# ST_LINK_V2-1.net
KiCad netlist of a schematic drawn in Altium Designer
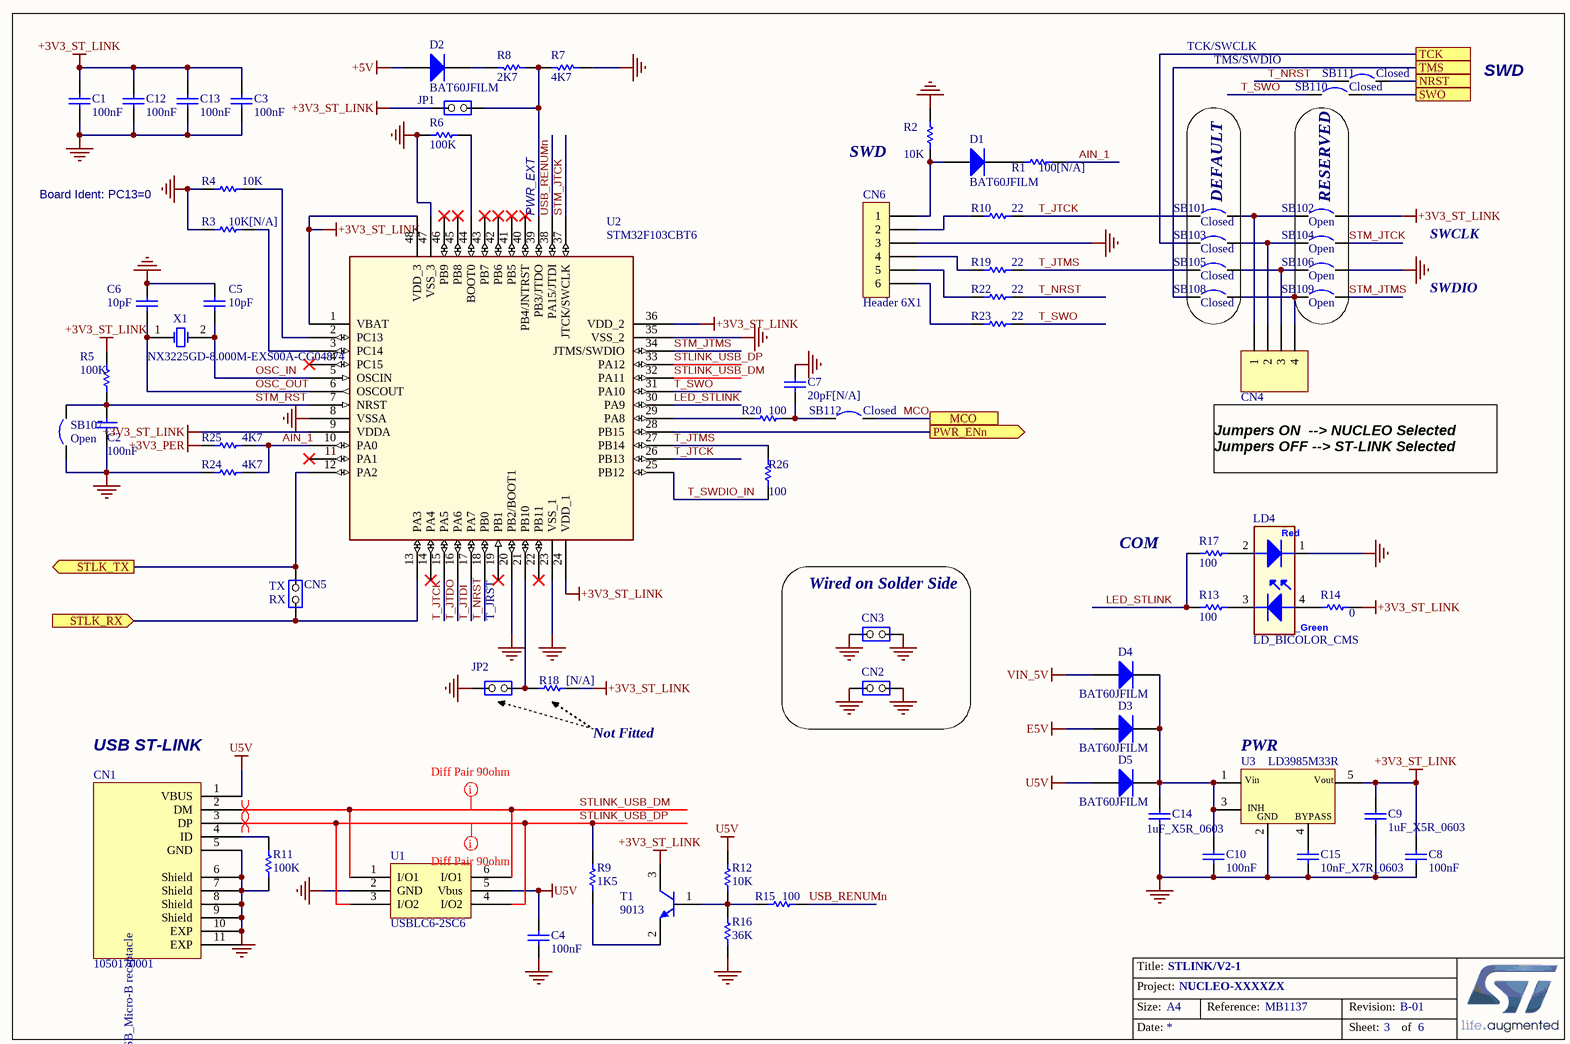
[diagram p0: ST_LINK_V2-1.SCHDOC]

(export (version "E")
  (design (tool "Eeschema 10.0.6"))
  (components
    (comp (ref "C1")
      (value "100nF")
      (footprint "0603C")
      (description "Capacitor 0402 / 0603 / 0805")
      (libsource (lib "MCD_TOOLS") (part "Capacitor_ST"))
    )
    (comp (ref "C2")
      (value "100nF")
      (footprint "0603C")
      (description "Capacitor 0402 / 0603 / 0805")
      (libsource (lib "MCD_TOOLS") (part "Capacitor_ST"))
    )
    (comp (ref "C3")
      (value "100nF")
      (footprint "0603C")
      (description "Capacitor 0402 / 0603 / 0805")
      (libsource (lib "MCD_TOOLS") (part "Capacitor_ST"))
    )
    (comp (ref "C4")
      (value "100nF")
      (footprint "0603C")
      (description "Capacitor 0402 / 0603 / 0805")
      (libsource (lib "MCD_TOOLS") (part "Capacitor_ST"))
    )
    (comp (ref "C5")
      (value "10pF")
      (footprint "0603C")
      (description "Capacitor 0402 / 0603 / 0805")
      (libsource (lib "MCD_TOOLS") (part "Capacitor_ST"))
    )
    (comp (ref "C6")
      (value "10pF")
      (footprint "0603C")
      (description "Capacitor 0402 / 0603 / 0805")
      (libsource (lib "MCD_TOOLS") (part "Capacitor_ST"))
    )
    (comp (ref "C7")
      (value "20pF[N/A]")
      (footprint "0603C")
      (description "Capacitor 0402 / 0603 / 0805")
      (libsource (lib "MCD_TOOLS") (part "Capacitor_ST"))
    )
    (comp (ref "C8")
      (value "100nF")
      (footprint "0603C")
      (description "Capacitor 0402 / 0603 / 0805")
      (libsource (lib "MCD_TOOLS") (part "Capacitor_ST"))
    )
    (comp (ref "C9")
      (value "1uF_X5R_0603")
      (footprint "0603C")
      (description "0603  X5R 1µF")
      (fields (field (name "TOLERANCE") "10%"))
      (libsource (lib "MB963_1") (part "CAP SMD 0603  X5R 1µF 25V 10%"))
    )
    (comp (ref "C10")
      (value "100nF")
      (footprint "0603C")
      (description "Capacitor 0402 / 0603 / 0805")
      (libsource (lib "MCD_TOOLS") (part "Capacitor_ST"))
    )
    (comp (ref "C12")
      (value "100nF")
      (footprint "0603C")
      (description "Capacitor 0402 / 0603 / 0805")
      (libsource (lib "MCD_TOOLS") (part "Capacitor_ST"))
    )
    (comp (ref "C13")
      (value "100nF")
      (footprint "0603C")
      (description "Capacitor 0402 / 0603 / 0805")
      (libsource (lib "MCD_TOOLS") (part "Capacitor_ST"))
    )
    (comp (ref "C14")
      (value "1uF_X5R_0603")
      (footprint "0603C")
      (description "0603  X5R 1µF")
      (fields (field (name "TOLERANCE") "10%"))
      (libsource (lib "MB963_1") (part "CAP SMD 0603  X5R 1µF 25V 10%"))
    )
    (comp (ref "C15")
      (value "10nF_X7R_0603")
      (footprint "0603C")
      (description "0603  X7R 10NF")
      (fields (field (name "TOLERANCE") "10%"))
      (libsource (lib "MB963_1") (part "CAP SMD 0603  X7R 10000PF 50V 10%"))
    )
    (comp (ref "CN1")
      (value "1050170001")
      (footprint "Molex_1050170001")
      (libsource (lib "Smartphone_accessory") (part "1050170001"))
    )
    (comp (ref "CN2") (value "~") (footprint "HDR_1x2_2R54_V_M") (libsource (lib "*") (part "JP2")))
    (comp (ref "CN3") (value "~") (footprint "HDR_1x2_2R54_V_M") (libsource (lib "*") (part "JP2")))
    (comp (ref "CN4")
      (value "Header 4")
      (footprint "HDR_1x4_2R54_V_M")
      (description "Header, 4-Pin, Single row")
      (fields (field (name "PUBLISHER") "Altium Limited"))
      (libsource (lib "Nucleo_64") (part "Header 4"))
    )
    (comp (ref "CN5") (value "~") (footprint "HDR_1x2_2R54_V_M_S") (libsource (lib "MCD_TOOLS") (part "JP2")))
    (comp (ref "CN6")
      (value "Header 6X1")
      (footprint "HDR_1x6_2R54_V_M")
      (description "Header, 6-Pin, Single row")
      (fields (field (name "PUBLISHER") "Altium Limited"))
      (libsource (lib "Nucleo_64") (part "Header 6X1"))
    )
    (comp (ref "D1")
      (value "BAT60JFILM")
      (footprint "SOD-323")
      (libsource (lib "MB1137") (part "BAT60JFILM"))
    )
    (comp (ref "D2")
      (value "BAT60JFILM")
      (footprint "SOD-323")
      (description "Default Diode")
      (fields (field (name "PUBLISHER") "Altium Limited"))
      (libsource (lib "MB1144_1") (part "Diode"))
    )
    (comp (ref "D3")
      (value "BAT60JFILM")
      (footprint "SOD-323")
      (libsource (lib "MB1137") (part "BAT60JFILM"))
    )
    (comp (ref "D4")
      (value "BAT60JFILM")
      (footprint "SOD-323")
      (libsource (lib "MB1137") (part "BAT60JFILM"))
    )
    (comp (ref "D5")
      (value "BAT60JFILM")
      (footprint "SOD-323")
      (libsource (lib "MB1137") (part "BAT60JFILM"))
    )
    (comp (ref "JP1") (value "~") (footprint "HDR_1x2_2R54_V_M_S") (libsource (lib "*") (part "JP2")))
    (comp (ref "JP2") (value "~") (footprint "HDR_1x2_2R54_V_M_S") (libsource (lib "*") (part "JP2")))
    (comp (ref "LD4")
      (value "LD_BICOLOR_CMS")
      (footprint "HSMF-A201")
      (description "Bicolor Led")
      (libsource (lib "MB1137") (part "LD_BICOLOR_CMS"))
    )
    (comp (ref "R1")
      (value "100[N/A]")
      (footprint "0603R")
      (description "Resistor 0402 / 0603 / 0805")
      (libsource (lib "") (part "Res1_1"))
    )
    (comp (ref "R2")
      (value "10K")
      (footprint "0603R")
      (description "Resistor 0402 / 0603 / 0805")
      (libsource (lib "") (part "Res1_1"))
    )
    (comp (ref "R3")
      (value "10K[N/A]")
      (footprint "0603R")
      (description "Resistor 0402 / 0603 / 0805")
      (libsource (lib "") (part "Res1_1"))
    )
    (comp (ref "R4")
      (value "10K")
      (footprint "0603R")
      (description "Resistor 0402 / 0603 / 0805")
      (libsource (lib "") (part "Res1_1"))
    )
    (comp (ref "R5")
      (value "100K")
      (footprint "0603R")
      (description "Resistor 0402 / 0603 / 0805")
      (libsource (lib "") (part "Res1_1"))
    )
    (comp (ref "R6")
      (value "100K")
      (footprint "0603R")
      (description "Resistor 0402 / 0603 / 0805")
      (libsource (lib "") (part "Res1_1"))
    )
    (comp (ref "R7")
      (value "4K7")
      (footprint "0603R")
      (description "Resistor")
      (fields (field (name "PUBLISHER") "Altium Limited"))
      (libsource (lib "Miscellaneous Devices") (part "Res1"))
    )
    (comp (ref "R8")
      (value "2K7")
      (footprint "0603R")
      (description "Resistor")
      (fields (field (name "PUBLISHER") "Altium Limited"))
      (libsource (lib "Miscellaneous Devices") (part "Res1"))
    )
    (comp (ref "R9")
      (value "1K5")
      (footprint "0603R")
      (description "Resistor 0402 / 0603 / 0805")
      (libsource (lib "") (part "Res1_1"))
    )
    (comp (ref "R10")
      (value "22")
      (footprint "0603R")
      (description "Resistor 0402 / 0603 / 0805")
      (libsource (lib "") (part "Res1_1"))
    )
    (comp (ref "R11")
      (value "100K")
      (footprint "0603R")
      (description "Resistor 0402 / 0603 / 0805")
      (libsource (lib "") (part "Res1_1"))
    )
    (comp (ref "R12")
      (value "10K")
      (footprint "0603R")
      (description "Resistor")
      (fields (field (name "PUBLISHER") "Altium Limited"))
      (libsource (lib "") (part "Res1_2"))
    )
    (comp (ref "R13")
      (value "100")
      (footprint "0603R")
      (description "Resistor 0402 / 0603 / 0805")
      (libsource (lib "") (part "Res1_1"))
    )
    (comp (ref "R14")
      (value "0")
      (footprint "0603R")
      (description "Resistor 0402 / 0603 / 0805")
      (libsource (lib "") (part "Res1_1"))
    )
    (comp (ref "R15")
      (value "100")
      (footprint "0603R")
      (description "Resistor 0402 / 0603 / 0805")
      (libsource (lib "") (part "Res1_1"))
    )
    (comp (ref "R16")
      (value "36K")
      (footprint "0603R")
      (description "Resistor")
      (fields (field (name "PUBLISHER") "Altium Limited"))
      (libsource (lib "") (part "Res1_2"))
    )
    (comp (ref "R17")
      (value "100")
      (footprint "0603R")
      (description "Resistor 0402 / 0603 / 0805")
      (libsource (lib "") (part "Res1_1"))
    )
    (comp (ref "R18")
      (value "[N/A]")
      (footprint "0603R")
      (description "Resistor")
      (fields (field (name "PUBLISHER") "Altium Limited"))
      (libsource (lib "") (part "Res1_2"))
    )
    (comp (ref "R19")
      (value "22")
      (footprint "0603R")
      (description "Resistor 0402 / 0603 / 0805")
      (libsource (lib "") (part "Res1_1"))
    )
    (comp (ref "R20")
      (value "100")
      (footprint "0603R")
      (description "Resistor 0402 / 0603 / 0805")
      (libsource (lib "") (part "Res1_1"))
    )
    (comp (ref "R22")
      (value "22")
      (footprint "0603R")
      (description "Resistor 0402 / 0603 / 0805")
      (libsource (lib "") (part "Res1_1"))
    )
    (comp (ref "R23")
      (value "22")
      (footprint "0603R")
      (description "Resistor 0402 / 0603 / 0805")
      (libsource (lib "") (part "Res1_1"))
    )
    (comp (ref "R24")
      (value "4K7")
      (footprint "0603R")
      (description "Resistor 0402 / 0603 / 0805")
      (libsource (lib "") (part "Res1_1"))
    )
    (comp (ref "R25")
      (value "4K7")
      (footprint "0603R")
      (description "Resistor 0402 / 0603 / 0805")
      (libsource (lib "") (part "Res1_1"))
    )
    (comp (ref "R26")
      (value "100")
      (footprint "0603R")
      (description "Resistor 0402 / 0603 / 0805")
      (libsource (lib "") (part "Res1_1"))
    )
    (comp (ref "SB101")
      (value "Closed")
      (footprint "SB_0603")
      (description "Circuit Breaker")
      (fields (field (name "PUBLISHER") "Altium Limited"))
      (libsource (lib "MB1167") (part "Circuit Breaker_close"))
    )
    (comp (ref "SB102")
      (value "Open")
      (footprint "SB_0603")
      (description "Circuit Breaker")
      (fields (field (name "PUBLISHER") "Altium Limited"))
      (libsource (lib "MB1167") (part "Circuit Breaker"))
    )
    (comp (ref "SB103")
      (value "Closed")
      (footprint "SB_0603")
      (description "Circuit Breaker")
      (fields (field (name "PUBLISHER") "Altium Limited"))
      (libsource (lib "MB1167") (part "Circuit Breaker_close"))
    )
    (comp (ref "SB104")
      (value "Open")
      (footprint "SB_0603")
      (description "Circuit Breaker")
      (fields (field (name "PUBLISHER") "Altium Limited"))
      (libsource (lib "MB1167") (part "Circuit Breaker"))
    )
    (comp (ref "SB105")
      (value "Closed")
      (footprint "SB_0603")
      (description "Circuit Breaker")
      (fields (field (name "PUBLISHER") "Altium Limited"))
      (libsource (lib "MB1167") (part "Circuit Breaker_close"))
    )
    (comp (ref "SB106")
      (value "Open")
      (footprint "SB_0603")
      (description "Circuit Breaker")
      (fields (field (name "PUBLISHER") "Altium Limited"))
      (libsource (lib "MB1167") (part "Circuit Breaker"))
    )
    (comp (ref "SB107")
      (value "Open")
      (footprint "SB_0603")
      (description "Circuit Breaker")
      (fields (field (name "PUBLISHER") "Altium Limited"))
      (libsource (lib "MB1167") (part "Circuit Breaker"))
    )
    (comp (ref "SB108")
      (value "Closed")
      (footprint "SB_0603")
      (description "Circuit Breaker")
      (fields (field (name "PUBLISHER") "Altium Limited"))
      (libsource (lib "MB1167") (part "Circuit Breaker_close"))
    )
    (comp (ref "SB109")
      (value "Open")
      (footprint "SB_0603")
      (description "Circuit Breaker")
      (fields (field (name "PUBLISHER") "Altium Limited"))
      (libsource (lib "MB1167") (part "Circuit Breaker"))
    )
    (comp (ref "SB110")
      (value "Closed")
      (footprint "SB_0603")
      (description "Circuit Breaker")
      (fields (field (name "PUBLISHER") "Altium Limited"))
      (libsource (lib "MB1167") (part "Circuit Breaker_close"))
    )
    (comp (ref "SB111")
      (value "Closed")
      (footprint "SB_0603")
      (description "Circuit Breaker")
      (fields (field (name "PUBLISHER") "Altium Limited"))
      (libsource (lib "MB1167") (part "Circuit Breaker_close"))
    )
    (comp (ref "SB112")
      (value "Closed")
      (footprint "SB_0603")
      (description "Circuit Breaker")
      (fields (field (name "PUBLISHER") "Altium Limited"))
      (libsource (lib "MB1167") (part "Circuit Breaker_close"))
    )
    (comp (ref "T1")
      (value "9013")
      (footprint "SOT-23")
      (description "NPN Bipolar Transistor")
      (fields (field (name "PUBLISHER") "Altium Limited"))
      (libsource (lib "MB1167") (part "NPN"))
    )
    (comp (ref "U1")
      (value "USBLC6-2SC6")
      (footprint "SOT23-6L")
      (libsource (lib "MB1137") (part "USBLC6-2SC6"))
    )
    (comp (ref "U2")
      (value "STM32F103CBT6")
      (footprint "LQFP48_0R5_7x7")
      (description "Medium-density performance line ARM-based 32-bit MCU with 64KB Flash")
      (libsource (lib "Nucleo_64") (part "STM32F103CBT6"))
    )
    (comp (ref "U3")
      (value "LD3985M33R")
      (footprint "SOT-23-5L")
      (description "Ultra low drop-low noise BiCMOS voltage, regulators low ESR capacitors compatible")
      (libsource (lib "MCD_TOOLS") (part "LD3985M33R"))
    )
    (comp (ref "X1")
      (value "NX3225GD-8.000M-EXS00A-CG04874")
      (footprint "OSC_2SM_3R2x2R5")
      (description "Crystal Oscillator")
      (fields (field (name "PUBLISHER") "Altium Limited"))
      (libsource (lib "MB963_1") (part "XTAL"))
    )
  )
  (nets
    (net (code "1") (name "+3V3_PER") (class "Default")
      (node (ref "R25") (pin "1") (pinfunction "1_1") (pintype "passive"))
    )
    (net (code "2") (name "+3V3_ST_LINK") (class "Default")
      (node (ref "C1") (pin "2") (pinfunction "2_2") (pintype "passive"))
      (node (ref "C12") (pin "2") (pinfunction "2_2") (pintype "passive"))
      (node (ref "C13") (pin "2") (pinfunction "2_2") (pintype "passive"))
      (node (ref "C3") (pin "2") (pinfunction "2_2") (pintype "passive"))
      (node (ref "C8") (pin "2") (pinfunction "2_2") (pintype "passive"))
      (node (ref "C9") (pin "1") (pinfunction "1_1") (pintype "passive"))
      (node (ref "JP1") (pin "1") (pinfunction "COMMON_1") (pintype "passive"))
      (node (ref "R14") (pin "2") (pinfunction "2_2") (pintype "passive"))
      (node (ref "R18") (pin "1") (pinfunction "1_1") (pintype "passive"))
      (node (ref "R5") (pin "2") (pinfunction "2_2") (pintype "passive"))
      (node (ref "SB102") (pin "2") (pinfunction "2_2") (pintype "passive"))
      (node (ref "T1") (pin "3") (pinfunction "C_3") (pintype "passive"))
      (node (ref "U2") (pin "1") (pinfunction "VBAT_1") (pintype "power_in"))
      (node (ref "U2") (pin "24") (pinfunction "VDD_1_24") (pintype "power_in"))
      (node (ref "U2") (pin "36") (pinfunction "VDD_2_36") (pintype "power_in"))
      (node (ref "U2") (pin "48") (pinfunction "VDD_3_48") (pintype "power_in"))
      (node (ref "U2") (pin "9") (pinfunction "VDDA_9") (pintype "power_in"))
      (node (ref "U3") (pin "5") (pinfunction "Vout_5") (pintype "passive"))
    )
    (net (code "3") (name "+5V") (class "Default")
      (node (ref "D2") (pin "1") (pinfunction "A_1") (pintype "passive"))
    )
    (net (code "4") (name "/AIN_1") (class "Default")
      (node (ref "R1") (pin "2") (pinfunction "2_2") (pintype "passive"))
      (node (ref "R24") (pin "2") (pinfunction "2_2") (pintype "passive"))
      (node (ref "R25") (pin "2") (pinfunction "2_2") (pintype "passive"))
      (node (ref "U2") (pin "10") (pinfunction "PA0_10") (pintype "bidirectional"))
    )
    (net (code "5") (name "/LED_STLINK") (class "Default")
      (node (ref "R13") (pin "1") (pinfunction "1_1") (pintype "passive"))
      (node (ref "R17") (pin "1") (pinfunction "1_1") (pintype "passive"))
      (node (ref "U2") (pin "30") (pinfunction "PA9_30") (pintype "bidirectional"))
    )
    (net (code "6") (name "/MCO") (class "Default")
      (node (ref "SB112") (pin "2") (pinfunction "2_2") (pintype "passive"))
    )
    (net (code "7") (name "/NRST") (class "Default")
      (node (ref "SB111") (pin "2") (pinfunction "2_2") (pintype "passive"))
    )
    (net (code "8") (name "/OSC_IN") (class "Default")
      (node (ref "C5") (pin "1") (pinfunction "1_1") (pintype "passive"))
      (node (ref "U2") (pin "5") (pinfunction "OSCIN_5") (pintype "input"))
      (node (ref "X1") (pin "2") (pinfunction "OSC2_2") (pintype "passive"))
    )
    (net (code "9") (name "/OSC_OUT") (class "Default")
      (node (ref "C6") (pin "1") (pinfunction "1_1") (pintype "passive"))
      (node (ref "U2") (pin "6") (pinfunction "OSCOUT_6") (pintype "output"))
      (node (ref "X1") (pin "1") (pinfunction "OSC1_1") (pintype "passive"))
    )
    (net (code "10") (name "/PWR_ENn") (class "Default")
      (node (ref "U2") (pin "28") (pinfunction "PB15_28") (pintype "bidirectional"))
    )
    (net (code "11") (name "/STLINK_USB_DM") (class "Default")
      (node (ref "CN1") (pin "2") (pinfunction "DM_2") (pintype "passive"))
      (node (ref "U1") (pin "1") (pinfunction "I/O1_1") (pintype "passive"))
      (node (ref "U1") (pin "6") (pinfunction "I/O1_6") (pintype "passive"))
      (node (ref "U2") (pin "32") (pinfunction "PA11_32") (pintype "bidirectional"))
    )
    (net (code "12") (name "/STLINK_USB_DP") (class "Default")
      (node (ref "CN1") (pin "3") (pinfunction "DP_3") (pintype "passive"))
      (node (ref "R9") (pin "1") (pinfunction "1_1") (pintype "passive"))
      (node (ref "U1") (pin "3") (pinfunction "I/O2_3") (pintype "passive"))
      (node (ref "U1") (pin "4") (pinfunction "I/O2_4") (pintype "passive"))
      (node (ref "U2") (pin "33") (pinfunction "PA12_33") (pintype "bidirectional"))
    )
    (net (code "13") (name "/STLK_RX") (class "Default")
      (node (ref "CN5") (pin "1") (pinfunction "COMMON_1") (pintype "passive"))
      (node (ref "U2") (pin "13") (pinfunction "PA3_13") (pintype "bidirectional"))
    )
    (net (code "14") (name "/STLK_TX") (class "Default")
      (node (ref "CN5") (pin "2") (pinfunction "NO_2") (pintype "passive"))
      (node (ref "U2") (pin "12") (pinfunction "PA2_12") (pintype "bidirectional"))
    )
    (net (code "15") (name "/STM_JTCK") (class "Default")
      (node (ref "SB104") (pin "2") (pinfunction "2_2") (pintype "passive"))
      (node (ref "U2") (pin "37") (pinfunction "JTCK/SWCLK_37") (pintype "bidirectional"))
    )
    (net (code "16") (name "/STM_JTMS") (class "Default")
      (node (ref "SB109") (pin "2") (pinfunction "2_2") (pintype "passive"))
      (node (ref "U2") (pin "34") (pinfunction "JTMS/SWDIO_34") (pintype "bidirectional"))
    )
    (net (code "17") (name "/STM_RST") (class "Default")
      (node (ref "C2") (pin "2") (pinfunction "2_2") (pintype "passive"))
      (node (ref "R5") (pin "1") (pinfunction "1_1") (pintype "passive"))
      (node (ref "SB107") (pin "2") (pinfunction "2_2") (pintype "passive"))
      (node (ref "U2") (pin "7") (pinfunction "NRST_7") (pintype "input"))
    )
    (net (code "18") (name "/SWO") (class "Default")
      (node (ref "SB110") (pin "2") (pinfunction "2_2") (pintype "passive"))
    )
    (net (code "19") (name "/TCK") (class "Default")
      (node (ref "SB103") (pin "1") (pinfunction "1_1") (pintype "passive"))
    )
    (net (code "20") (name "/TMS") (class "Default")
      (node (ref "SB108") (pin "1") (pinfunction "1_1") (pintype "passive"))
    )
    (net (code "21") (name "/T_JTCK") (class "Default")
      (node (ref "R10") (pin "2") (pinfunction "2_2") (pintype "passive"))
      (node (ref "SB101") (pin "1") (pinfunction "1_1") (pintype "passive"))
      (node (ref "U2") (pin "15") (pinfunction "PA5_15") (pintype "bidirectional"))
      (node (ref "U2") (pin "26") (pinfunction "PB13_26") (pintype "bidirectional"))
    )
    (net (code "22") (name "/T_JTDI") (class "Default")
      (node (ref "U2") (pin "17") (pinfunction "PA7_17") (pintype "bidirectional"))
    )
    (net (code "23") (name "/T_JTDO") (class "Default")
      (node (ref "U2") (pin "16") (pinfunction "PA6_16") (pintype "bidirectional"))
    )
    (net (code "24") (name "/T_JTMS") (class "Default")
      (node (ref "R19") (pin "2") (pinfunction "2_2") (pintype "passive"))
      (node (ref "R26") (pin "2") (pinfunction "2_2") (pintype "passive"))
      (node (ref "SB105") (pin "1") (pinfunction "1_1") (pintype "passive"))
      (node (ref "U2") (pin "27") (pinfunction "PB14_27") (pintype "bidirectional"))
    )
    (net (code "25") (name "/T_NRST") (class "Default")
      (node (ref "R22") (pin "2") (pinfunction "2_2") (pintype "passive"))
      (node (ref "SB111") (pin "1") (pinfunction "1_1") (pintype "passive"))
      (node (ref "U2") (pin "18") (pinfunction "PB0_18") (pintype "bidirectional"))
    )
    (net (code "26") (name "/T_SWDIO_IN") (class "Default")
      (node (ref "R26") (pin "1") (pinfunction "1_1") (pintype "passive"))
      (node (ref "U2") (pin "25") (pinfunction "PB12_25") (pintype "bidirectional"))
    )
    (net (code "27") (name "/T_SWO") (class "Default")
      (node (ref "R23") (pin "2") (pinfunction "2_2") (pintype "passive"))
      (node (ref "SB110") (pin "1") (pinfunction "1_1") (pintype "passive"))
      (node (ref "U2") (pin "31") (pinfunction "PA10_31") (pintype "bidirectional"))
    )
    (net (code "28") (name "/USB_RENUMn") (class "Default")
      (node (ref "R15") (pin "2") (pinfunction "2_2") (pintype "passive"))
      (node (ref "U2") (pin "38") (pinfunction "PA15/JTDI_38") (pintype "bidirectional"))
    )
    (net (code "29") (name "E5V") (class "Default")
      (node (ref "D3") (pin "1") (pinfunction "A_1") (pintype "passive"))
    )
    (net (code "30") (name "GND") (class "Default")
      (node (ref "C1") (pin "1") (pinfunction "1_1") (pintype "passive"))
      (node (ref "C10") (pin "1") (pinfunction "1_1") (pintype "passive"))
      (node (ref "C12") (pin "1") (pinfunction "1_1") (pintype "passive"))
      (node (ref "C13") (pin "1") (pinfunction "1_1") (pintype "passive"))
      (node (ref "C14") (pin "1") (pinfunction "1_1") (pintype "passive"))
      (node (ref "C15") (pin "1") (pinfunction "1_1") (pintype "passive"))
      (node (ref "C2") (pin "1") (pinfunction "1_1") (pintype "passive"))
      (node (ref "C3") (pin "1") (pinfunction "1_1") (pintype "passive"))
      (node (ref "C4") (pin "1") (pinfunction "1_1") (pintype "passive"))
      (node (ref "C5") (pin "2") (pinfunction "2_2") (pintype "passive"))
      (node (ref "C6") (pin "2") (pinfunction "2_2") (pintype "passive"))
      (node (ref "C7") (pin "2") (pinfunction "2_2") (pintype "passive"))
      (node (ref "C8") (pin "1") (pinfunction "1_1") (pintype "passive"))
      (node (ref "C9") (pin "2") (pinfunction "2_2") (pintype "passive"))
      (node (ref "CN1") (pin "10") (pinfunction "EXP_10") (pintype "passive"))
      (node (ref "CN1") (pin "5") (pinfunction "GND_5") (pintype "passive"))
      (node (ref "CN1") (pin "6") (pinfunction "Shield_6") (pintype "passive"))
      (node (ref "CN1") (pin "7") (pinfunction "Shield_7") (pintype "passive"))
      (node (ref "CN1") (pin "8") (pinfunction "Shield_8") (pintype "passive"))
      (node (ref "CN1") (pin "9") (pinfunction "Shield_9") (pintype "passive"))
      (node (ref "CN2") (pin "1") (pinfunction "COMMON_1") (pintype "passive"))
      (node (ref "CN2") (pin "2") (pinfunction "NO_2") (pintype "passive"))
      (node (ref "CN3") (pin "1") (pinfunction "COMMON_1") (pintype "passive"))
      (node (ref "CN3") (pin "2") (pinfunction "NO_2") (pintype "passive"))
      (node (ref "CN6") (pin "3") (pinfunction "3_3") (pintype "passive"))
      (node (ref "JP2") (pin "1") (pinfunction "COMMON_1") (pintype "passive"))
      (node (ref "LD4") (pin "1") (pinfunction "1_1") (pintype "passive"))
      (node (ref "R11") (pin "2") (pinfunction "2_2") (pintype "passive"))
      (node (ref "R16") (pin "1") (pinfunction "1_1") (pintype "passive"))
      (node (ref "R2") (pin "2") (pinfunction "2_2") (pintype "passive"))
      (node (ref "R24") (pin "1") (pinfunction "1_1") (pintype "passive"))
      (node (ref "R3") (pin "1") (pinfunction "1_1") (pintype "passive"))
      (node (ref "R4") (pin "1") (pinfunction "1_1") (pintype "passive"))
      (node (ref "R6") (pin "1") (pinfunction "1_1") (pintype "passive"))
      (node (ref "R7") (pin "2") (pinfunction "2_2") (pintype "passive"))
      (node (ref "SB106") (pin "2") (pinfunction "2_2") (pintype "passive"))
      (node (ref "SB107") (pin "1") (pinfunction "1_1") (pintype "passive"))
      (node (ref "U1") (pin "2") (pinfunction "GND_2") (pintype "passive"))
      (node (ref "U2") (pin "20") (pinfunction "PB2/BOOT1_20") (pintype "bidirectional"))
      (node (ref "U2") (pin "23") (pinfunction "VSS_1_23") (pintype "power_in"))
      (node (ref "U2") (pin "35") (pinfunction "VSS_2_35") (pintype "power_in"))
      (node (ref "U2") (pin "47") (pinfunction "VSS_3_47") (pintype "power_in"))
      (node (ref "U2") (pin "8") (pinfunction "VSSA_8") (pintype "power_in"))
      (node (ref "U3") (pin "2") (pinfunction "GND_2") (pintype "passive"))
    )
    (net (code "31") (name "Net-(C7-Pad1)") (class "Default")
      (node (ref "C7") (pin "1") (pinfunction "1_1") (pintype "passive"))
      (node (ref "R20") (pin "2") (pinfunction "2_2") (pintype "passive"))
      (node (ref "SB112") (pin "1") (pinfunction "1_1") (pintype "passive"))
    )
    (net (code "32") (name "Net-(CN1-ID)") (class "Default")
      (node (ref "CN1") (pin "4") (pinfunction "ID_4") (pintype "passive"))
      (node (ref "R11") (pin "1") (pinfunction "1_1") (pintype "passive"))
    )
    (net (code "33") (name "Net-(CN4-Pad1)") (class "Default")
      (node (ref "CN4") (pin "1") (pinfunction "1_1") (pintype "passive"))
      (node (ref "SB101") (pin "2") (pinfunction "2_2") (pintype "passive"))
      (node (ref "SB102") (pin "1") (pinfunction "1_1") (pintype "passive"))
    )
    (net (code "34") (name "Net-(CN4-Pad2)") (class "Default")
      (node (ref "CN4") (pin "2") (pinfunction "2_2") (pintype "passive"))
      (node (ref "SB103") (pin "2") (pinfunction "2_2") (pintype "passive"))
      (node (ref "SB104") (pin "1") (pinfunction "1_1") (pintype "passive"))
    )
    (net (code "35") (name "Net-(CN4-Pad3)") (class "Default")
      (node (ref "CN4") (pin "3") (pinfunction "3_3") (pintype "passive"))
      (node (ref "SB105") (pin "2") (pinfunction "2_2") (pintype "passive"))
      (node (ref "SB106") (pin "1") (pinfunction "1_1") (pintype "passive"))
    )
    (net (code "36") (name "Net-(CN4-Pad4)") (class "Default")
      (node (ref "CN4") (pin "4") (pinfunction "4_4") (pintype "passive"))
      (node (ref "SB108") (pin "2") (pinfunction "2_2") (pintype "passive"))
      (node (ref "SB109") (pin "1") (pinfunction "1_1") (pintype "passive"))
    )
    (net (code "37") (name "Net-(CN6-Pad2)") (class "Default")
      (node (ref "CN6") (pin "2") (pinfunction "2_2") (pintype "passive"))
      (node (ref "R10") (pin "1") (pinfunction "1_1") (pintype "passive"))
    )
    (net (code "38") (name "Net-(CN6-Pad4)") (class "Default")
      (node (ref "CN6") (pin "4") (pinfunction "4_4") (pintype "passive"))
      (node (ref "R19") (pin "1") (pinfunction "1_1") (pintype "passive"))
    )
    (net (code "39") (name "Net-(CN6-Pad5)") (class "Default")
      (node (ref "CN6") (pin "5") (pinfunction "5_5") (pintype "passive"))
      (node (ref "R22") (pin "1") (pinfunction "1_1") (pintype "passive"))
    )
    (net (code "40") (name "Net-(CN6-Pad6)") (class "Default")
      (node (ref "CN6") (pin "6") (pinfunction "6_6") (pintype "passive"))
      (node (ref "R23") (pin "1") (pinfunction "1_1") (pintype "passive"))
    )
    (net (code "41") (name "Net-(D1-A)") (class "Default")
      (node (ref "CN6") (pin "1") (pinfunction "1_1") (pintype "passive"))
      (node (ref "D1") (pin "1") (pinfunction "A_1") (pintype "passive"))
      (node (ref "R2") (pin "1") (pinfunction "1_1") (pintype "passive"))
    )
    (net (code "42") (name "Net-(D1-K)") (class "Default")
      (node (ref "D1") (pin "2") (pinfunction "K_2") (pintype "passive"))
      (node (ref "R1") (pin "1") (pinfunction "1_1") (pintype "passive"))
    )
    (net (code "43") (name "Net-(D2-K)") (class "Default")
      (node (ref "D2") (pin "2") (pinfunction "K_2") (pintype "passive"))
      (node (ref "R8") (pin "1") (pinfunction "1_1") (pintype "passive"))
    )
    (net (code "44") (name "Net-(D3-K)") (class "Default")
      (node (ref "C10") (pin "2") (pinfunction "2_2") (pintype "passive"))
      (node (ref "C14") (pin "2") (pinfunction "2_2") (pintype "passive"))
      (node (ref "D3") (pin "2") (pinfunction "K_2") (pintype "passive"))
      (node (ref "D4") (pin "2") (pinfunction "K_2") (pintype "passive"))
      (node (ref "D5") (pin "2") (pinfunction "K_2") (pintype "passive"))
      (node (ref "U3") (pin "1") (pinfunction "Vin_1") (pintype "passive"))
      (node (ref "U3") (pin "3") (pinfunction "CE_3") (pintype "passive"))
    )
    (net (code "45") (name "Net-(JP1-NO)") (class "Default")
      (node (ref "JP1") (pin "2") (pinfunction "NO_2") (pintype "passive"))
      (node (ref "R7") (pin "1") (pinfunction "1_1") (pintype "passive"))
      (node (ref "R8") (pin "2") (pinfunction "2_2") (pintype "passive"))
      (node (ref "U2") (pin "39") (pinfunction "PB3/JTDO_39") (pintype "bidirectional"))
    )
    (net (code "46") (name "Net-(JP2-NO)") (class "Default")
      (node (ref "JP2") (pin "2") (pinfunction "NO_2") (pintype "passive"))
      (node (ref "R18") (pin "2") (pinfunction "2_2") (pintype "passive"))
      (node (ref "U2") (pin "21") (pinfunction "PB10_21") (pintype "bidirectional"))
    )
    (net (code "47") (name "Net-(LD4-Pad2)") (class "Default")
      (node (ref "LD4") (pin "2") (pinfunction "2_2") (pintype "passive"))
      (node (ref "R17") (pin "2") (pinfunction "2_2") (pintype "passive"))
    )
    (net (code "48") (name "Net-(LD4-Pad3)") (class "Default")
      (node (ref "LD4") (pin "3") (pinfunction "3_3") (pintype "passive"))
      (node (ref "R13") (pin "2") (pinfunction "2_2") (pintype "passive"))
    )
    (net (code "49") (name "Net-(LD4-Pad4)") (class "Default")
      (node (ref "LD4") (pin "4") (pinfunction "4_4") (pintype "passive"))
      (node (ref "R14") (pin "1") (pinfunction "1_1") (pintype "passive"))
    )
    (net (code "50") (name "Net-(T1-B)") (class "Default")
      (node (ref "R12") (pin "1") (pinfunction "1_1") (pintype "passive"))
      (node (ref "R15") (pin "1") (pinfunction "1_1") (pintype "passive"))
      (node (ref "R16") (pin "2") (pinfunction "2_2") (pintype "passive"))
      (node (ref "T1") (pin "1") (pinfunction "B_1") (pintype "passive"))
    )
    (net (code "51") (name "Net-(T1-E)") (class "Default")
      (node (ref "R9") (pin "2") (pinfunction "2_2") (pintype "passive"))
      (node (ref "T1") (pin "2") (pinfunction "E_2") (pintype "passive"))
    )
    (net (code "52") (name "Net-(U2-BOOT0)") (class "Default")
      (node (ref "R6") (pin "2") (pinfunction "2_2") (pintype "passive"))
      (node (ref "U2") (pin "44") (pinfunction "BOOT0_44") (pintype "bidirectional"))
    )
    (net (code "53") (name "Net-(U2-PA8)") (class "Default")
      (node (ref "R20") (pin "1") (pinfunction "1_1") (pintype "passive"))
      (node (ref "U2") (pin "29") (pinfunction "PA8_29") (pintype "bidirectional"))
    )
    (net (code "54") (name "Net-(U2-PC13)") (class "Default")
      (node (ref "R4") (pin "2") (pinfunction "2_2") (pintype "passive"))
      (node (ref "U2") (pin "2") (pinfunction "PC13_2") (pintype "bidirectional"))
    )
    (net (code "55") (name "Net-(U2-PC14)") (class "Default")
      (node (ref "R3") (pin "2") (pinfunction "2_2") (pintype "passive"))
      (node (ref "U2") (pin "3") (pinfunction "PC14_3") (pintype "bidirectional"))
    )
    (net (code "56") (name "Net-(U3-BYPASS)") (class "Default")
      (node (ref "C15") (pin "2") (pinfunction "2_2") (pintype "passive"))
      (node (ref "U3") (pin "4") (pinfunction "BYPASS_4") (pintype "passive"))
    )
    (net (code "57") (name "U5V") (class "Default")
      (node (ref "C4") (pin "2") (pinfunction "2_2") (pintype "passive"))
      (node (ref "CN1") (pin "1") (pinfunction "VBUS_1") (pintype "passive"))
      (node (ref "D5") (pin "1") (pinfunction "A_1") (pintype "passive"))
      (node (ref "R12") (pin "2") (pinfunction "2_2") (pintype "passive"))
      (node (ref "U1") (pin "5") (pinfunction "Vbus_5") (pintype "passive"))
    )
    (net (code "58") (name "VIN_5V") (class "Default")
      (node (ref "D4") (pin "1") (pinfunction "A_1") (pintype "passive"))
    )
    (net (code "59") (name "unconnected-(CN1-EXP-Pad11)") (class "Default")
      (node (ref "CN1") (pin "11") (pinfunction "EXP_11") (pintype "passive"))
    )
    (net (code "60") (name "unconnected-(U2-PA1-Pad11)") (class "Default")
      (node (ref "U2") (pin "11") (pinfunction "PA1_11") (pintype "bidirectional+no_connect"))
    )
    (net (code "61") (name "unconnected-(U2-PA4-Pad14)") (class "Default")
      (node (ref "U2") (pin "14") (pinfunction "PA4_14") (pintype "bidirectional+no_connect"))
    )
    (net (code "62") (name "unconnected-(U2-PB1-Pad19)") (class "Default")
      (node (ref "U2") (pin "19") (pinfunction "PB1_19") (pintype "input+no_connect"))
    )
    (net (code "63") (name "unconnected-(U2-PB4{slash}JNTRST-Pad40)") (class "Default")
      (node (ref "U2") (pin "40") (pinfunction "PB4/JNTRST_40") (pintype "bidirectional+no_connect"))
    )
    (net (code "64") (name "unconnected-(U2-PB5-Pad41)") (class "Default")
      (node (ref "U2") (pin "41") (pinfunction "PB5_41") (pintype "bidirectional+no_connect"))
    )
    (net (code "65") (name "unconnected-(U2-PB6-Pad42)") (class "Default")
      (node (ref "U2") (pin "42") (pinfunction "PB6_42") (pintype "bidirectional+no_connect"))
    )
    (net (code "66") (name "unconnected-(U2-PB7-Pad43)") (class "Default")
      (node (ref "U2") (pin "43") (pinfunction "PB7_43") (pintype "bidirectional+no_connect"))
    )
    (net (code "67") (name "unconnected-(U2-PB8-Pad45)") (class "Default")
      (node (ref "U2") (pin "45") (pinfunction "PB8_45") (pintype "bidirectional+no_connect"))
    )
    (net (code "68") (name "unconnected-(U2-PB9-Pad46)") (class "Default")
      (node (ref "U2") (pin "46") (pinfunction "PB9_46") (pintype "bidirectional+no_connect"))
    )
    (net (code "69") (name "unconnected-(U2-PB11-Pad22)") (class "Default")
      (node (ref "U2") (pin "22") (pinfunction "PB11_22") (pintype "bidirectional+no_connect"))
    )
    (net (code "70") (name "unconnected-(U2-PC15-Pad4)") (class "Default")
      (node (ref "U2") (pin "4") (pinfunction "PC15_4") (pintype "bidirectional+no_connect"))
    )
  )
)
